# onion_dip_v2.net
KiCad netlist of a schematic drawn in EAGLE
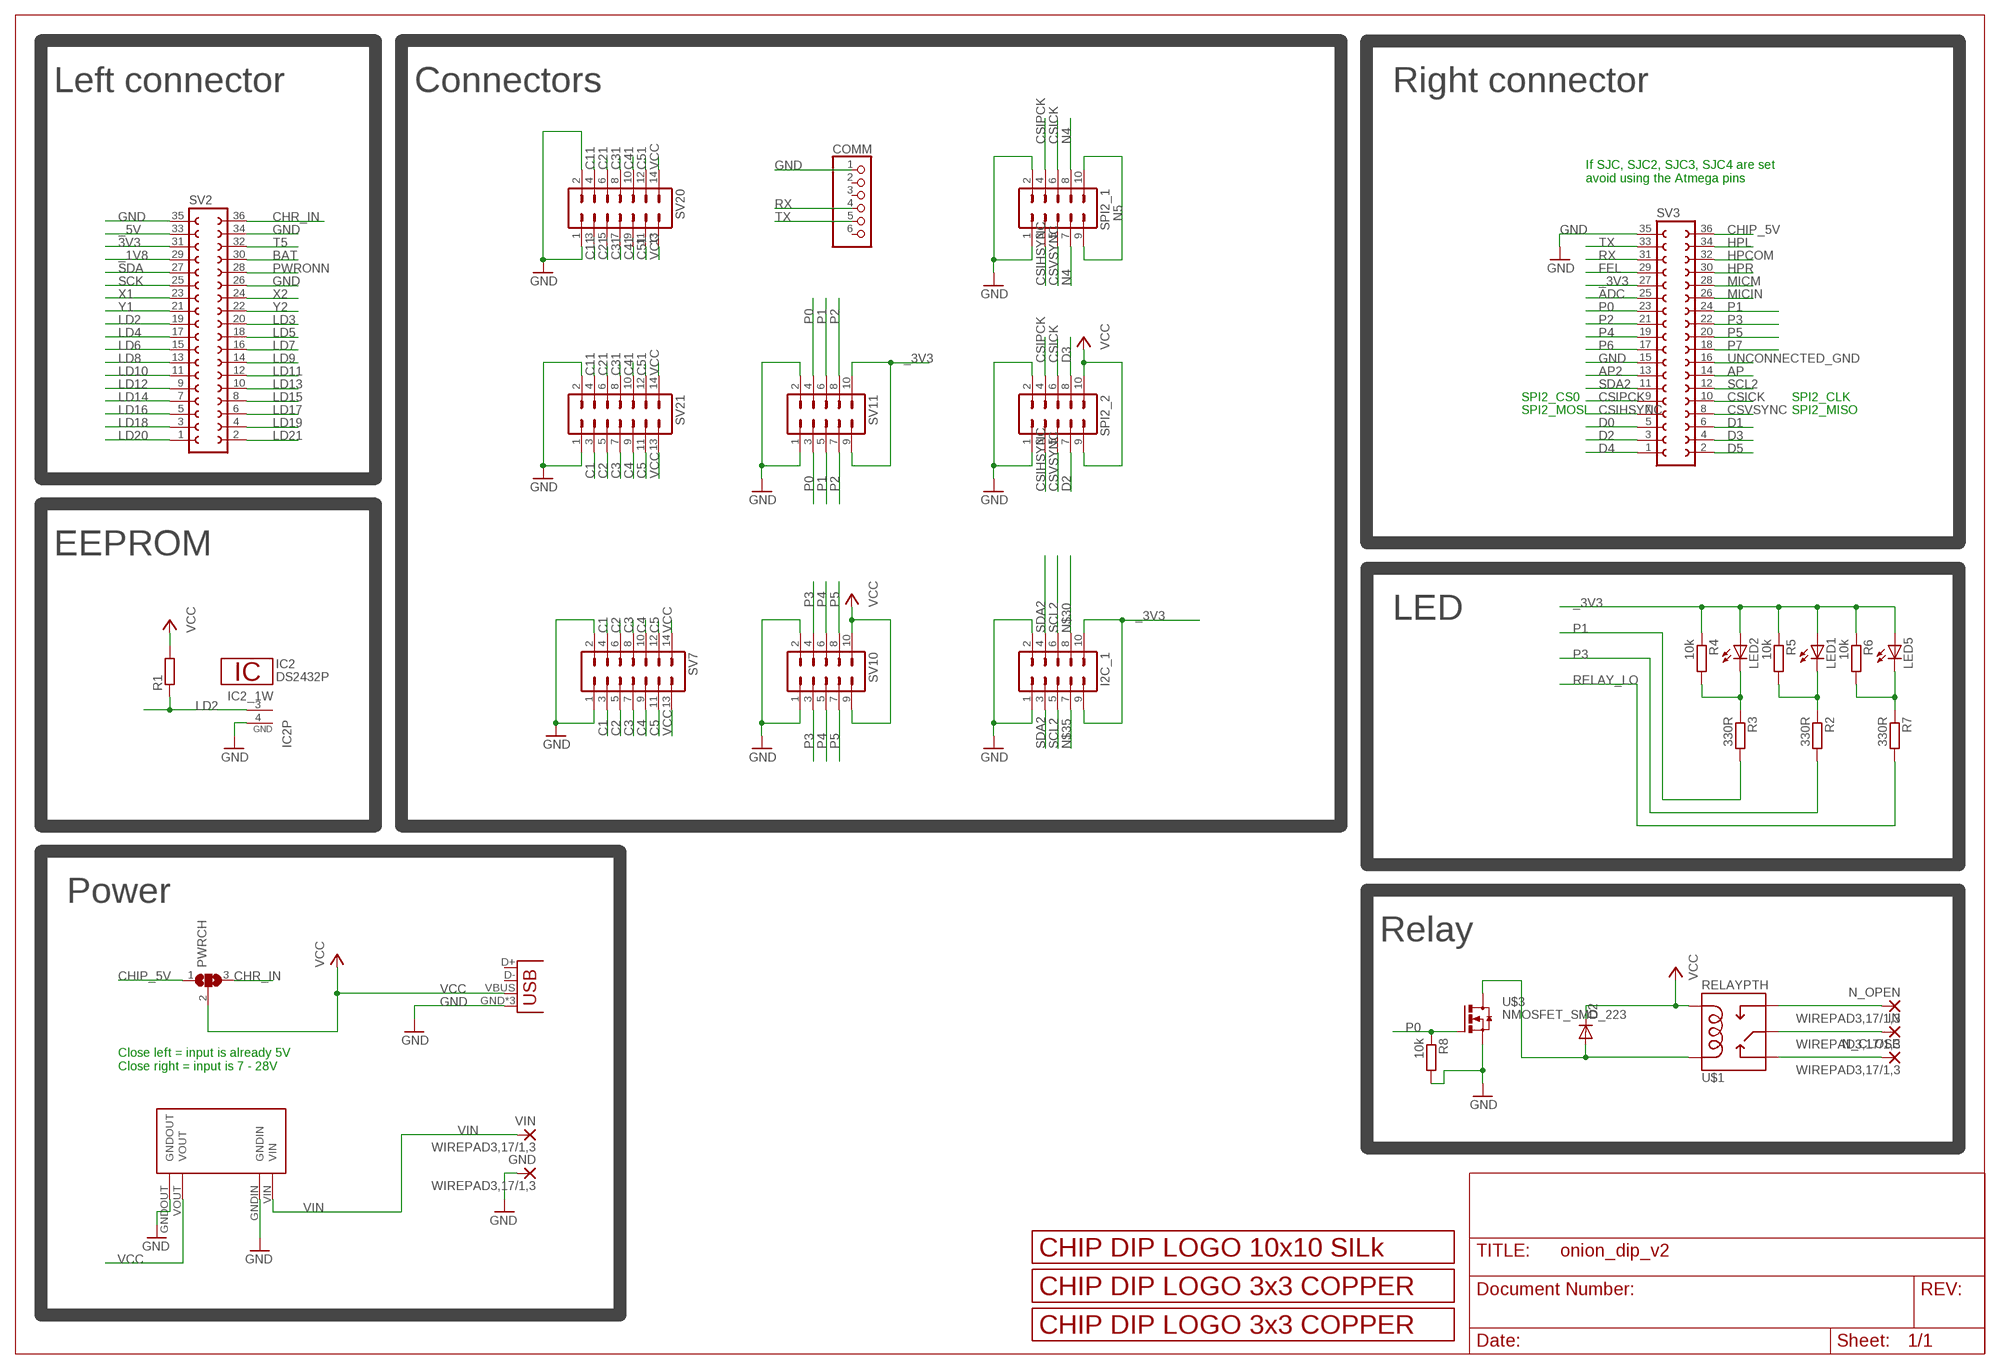
[diagram p0: schematic, sheet 1]

(export (version "E")
  (design (tool "Eeschema 10.0.6"))
  (components
    (comp (ref "COMM")
      (value "PINHD-1X6")
      (footprint "eagle-import:1X06")
      (libsource (lib "eagle-import") (part "PINHD-1X6"))
    )
    (comp (ref "D2")
      (value "DIODE-SMB")
      (footprint "eagle-import:SMB")
      (libsource (lib "eagle-import") (part "DIODE-SMB"))
    )
    (comp (ref "GND")
      (value "WIREPAD3,17/1,3")
      (footprint "eagle-import:3,17_1,3")
      (libsource (lib "eagle-import") (part "WIREPAD3,17/1,3"))
    )
    (comp (ref "I2C_1")
      (value "MA05-2")
      (footprint "eagle-import:MA05-2")
      (libsource (lib "eagle-import") (part "MA05-2"))
    )
    (comp (ref "IC2")
      (value "DS2432P")
      (footprint "eagle-import:TSOC6")
      (libsource (lib "eagle-import") (part "DS2432P"))
    )
    (comp (ref "IN")
      (value "WIREPAD3,17/1,3")
      (footprint "eagle-import:3,17_1,3")
      (libsource (lib "eagle-import") (part "WIREPAD3,17/1,3"))
    )
    (comp (ref "LED1")
      (value "LEDCHIP-LED0805")
      (footprint "eagle-import:CHIP-LED0805")
      (libsource (lib "eagle-import") (part "LEDCHIP-LED0805"))
    )
    (comp (ref "LED2")
      (value "LEDCHIP-LED0805")
      (footprint "eagle-import:CHIP-LED0805")
      (libsource (lib "eagle-import") (part "LEDCHIP-LED0805"))
    )
    (comp (ref "LED5")
      (value "LEDCHIP-LED0805")
      (footprint "eagle-import:CHIP-LED0805")
      (libsource (lib "eagle-import") (part "LEDCHIP-LED0805"))
    )
    (comp (ref "N_CLOSE")
      (value "WIREPAD3,17/1,3")
      (footprint "eagle-import:3,17_1,3")
      (libsource (lib "eagle-import") (part "WIREPAD3,17/1,3"))
    )
    (comp (ref "N_OPEN")
      (value "WIREPAD3,17/1,3")
      (footprint "eagle-import:3,17_1,3")
      (libsource (lib "eagle-import") (part "WIREPAD3,17/1,3"))
    )
    (comp (ref "PWRCH")
      (value "SJ2W")
      (footprint "eagle-import:SJ_2")
      (libsource (lib "eagle-import") (part "SJ2W"))
    )
    (comp (ref "R1")
      (value "R-EU_R0805")
      (footprint "eagle-import:R0805")
      (libsource (lib "eagle-import") (part "R-EU_R0805"))
    )
    (comp (ref "R2")
      (value "330R")
      (footprint "eagle-import:R0805")
      (libsource (lib "eagle-import") (part "R-EU_R0805"))
    )
    (comp (ref "R3")
      (value "330R")
      (footprint "eagle-import:R0805")
      (libsource (lib "eagle-import") (part "R-EU_R0805"))
    )
    (comp (ref "R4")
      (value "10k")
      (footprint "eagle-import:R0805")
      (libsource (lib "eagle-import") (part "R-EU_R0805"))
    )
    (comp (ref "R5")
      (value "10k")
      (footprint "eagle-import:R0805")
      (libsource (lib "eagle-import") (part "R-EU_R0805"))
    )
    (comp (ref "R6")
      (value "10k")
      (footprint "eagle-import:R0805")
      (libsource (lib "eagle-import") (part "R-EU_R0805"))
    )
    (comp (ref "R7")
      (value "330R")
      (footprint "eagle-import:R0805")
      (libsource (lib "eagle-import") (part "R-EU_R0805"))
    )
    (comp (ref "R8")
      (value "10k")
      (footprint "eagle-import:R0805")
      (libsource (lib "eagle-import") (part "R-EU_R0805"))
    )
    (comp (ref "SPI2_1")
      (value "MA05-2")
      (footprint "eagle-import:MA05-2")
      (libsource (lib "eagle-import") (part "MA05-2"))
    )
    (comp (ref "SPI2_2")
      (value "MA05-2")
      (footprint "eagle-import:MA05-2")
      (libsource (lib "eagle-import") (part "MA05-2"))
    )
    (comp (ref "SV2")
      (value "FE18-2")
      (footprint "eagle-import:FE18-2")
      (libsource (lib "eagle-import") (part "FE18-2"))
    )
    (comp (ref "SV3")
      (value "FE18-2")
      (footprint "eagle-import:FE18-2")
      (libsource (lib "eagle-import") (part "FE18-2"))
    )
    (comp (ref "SV7")
      (value "MA07-2")
      (footprint "eagle-import:MA07-2")
      (libsource (lib "eagle-import") (part "MA07-2"))
    )
    (comp (ref "SV10")
      (value "MA05-2")
      (footprint "eagle-import:MA05-2")
      (libsource (lib "eagle-import") (part "MA05-2"))
    )
    (comp (ref "SV11")
      (value "MA05-2")
      (footprint "eagle-import:MA05-2")
      (libsource (lib "eagle-import") (part "MA05-2"))
    )
    (comp (ref "SV20")
      (value "MA07-2")
      (footprint "eagle-import:MA07-2")
      (libsource (lib "eagle-import") (part "MA07-2"))
    )
    (comp (ref "SV21")
      (value "MA07-2")
      (footprint "eagle-import:MA07-2")
      (libsource (lib "eagle-import") (part "MA07-2"))
    )
    (comp (ref "U$1")
      (value "RELAYPTH")
      (footprint "eagle-import:SRD-05VDC-SL-C")
      (libsource (lib "eagle-import") (part "RELAYPTH"))
    )
    (comp (ref "U$3")
      (value "NMOSFET_SMD_223")
      (footprint "eagle-import:SOT223")
      (libsource (lib "eagle-import") (part "NMOSFET_SMD_223"))
    )
    (comp (ref "U$4")
      (value "LOGO_3X3_COPPER")
      (footprint "eagle-import:LOGO_3X3_COPPER")
      (libsource (lib "eagle-import") (part "LOGO_3X3_COPPER"))
    )
    (comp (ref "U$5")
      (value "LOGO_10X10_SILK")
      (footprint "eagle-import:LOGO_10X10_SILK")
      (libsource (lib "eagle-import") (part "LOGO_10X10_SILK"))
    )
    (comp (ref "U$6")
      (value "LOGO_3X3_COPPER")
      (footprint "eagle-import:LOGO_3X3_COPPER")
      (libsource (lib "eagle-import") (part "LOGO_3X3_COPPER"))
    )
    (comp (ref "U$9")
      (value "MP1584EN_FRAMELESS")
      (footprint "eagle-import:MP1584EN_FRAMELESS")
      (libsource (lib "eagle-import") (part "MP1584EN_FRAMELESS"))
    )
    (comp (ref "USB")
      (value "USBUSB-MICROB-SMT-DIP")
      (footprint "eagle-import:USB-MICROB-SMT-DIP")
      (libsource (lib "eagle-import") (part "USBUSB-MICROB-SMT-DIP"))
    )
    (comp (ref "VIN")
      (value "WIREPAD3,17/1,3")
      (footprint "eagle-import:3,17_1,3")
      (libsource (lib "eagle-import") (part "WIREPAD3,17/1,3"))
    )
  )
  (nets
    (net (code "1") (name "/3V3") (class "Default")
      (node (ref "SV2") (pin "31") (pinfunction "31_31") (pintype "passive"))
    )
    (net (code "2") (name "/ADC") (class "Default")
      (node (ref "SV3") (pin "25") (pinfunction "25_25") (pintype "passive"))
    )
    (net (code "3") (name "/AP") (class "Default")
      (node (ref "SV3") (pin "14") (pinfunction "14_14") (pintype "passive"))
    )
    (net (code "4") (name "/AP2") (class "Default")
      (node (ref "SV3") (pin "13") (pinfunction "13_13") (pintype "passive"))
    )
    (net (code "5") (name "/BAT") (class "Default")
      (node (ref "SV2") (pin "30") (pinfunction "30_30") (pintype "passive"))
    )
    (net (code "6") (name "/C1") (class "Default")
      (node (ref "SV21") (pin "3") (pinfunction "3_3") (pintype "passive"))
      (node (ref "SV7") (pin "3") (pinfunction "3_3") (pintype "passive"))
      (node (ref "SV7") (pin "4") (pinfunction "4_4") (pintype "passive"))
    )
    (net (code "7") (name "/C2") (class "Default")
      (node (ref "SV21") (pin "5") (pinfunction "5_5") (pintype "passive"))
      (node (ref "SV7") (pin "5") (pinfunction "5_5") (pintype "passive"))
      (node (ref "SV7") (pin "6") (pinfunction "6_6") (pintype "passive"))
    )
    (net (code "8") (name "/C3") (class "Default")
      (node (ref "SV21") (pin "7") (pinfunction "7_7") (pintype "passive"))
      (node (ref "SV7") (pin "7") (pinfunction "7_7") (pintype "passive"))
      (node (ref "SV7") (pin "8") (pinfunction "8_8") (pintype "passive"))
    )
    (net (code "9") (name "/C4") (class "Default")
      (node (ref "SV21") (pin "9") (pinfunction "9_9") (pintype "passive"))
      (node (ref "SV7") (pin "10") (pinfunction "10_10") (pintype "passive"))
      (node (ref "SV7") (pin "9") (pinfunction "9_9") (pintype "passive"))
    )
    (net (code "10") (name "/C5") (class "Default")
      (node (ref "SV21") (pin "11") (pinfunction "11_11") (pintype "passive"))
      (node (ref "SV7") (pin "11") (pinfunction "11_11") (pintype "passive"))
      (node (ref "SV7") (pin "12") (pinfunction "12_12") (pintype "passive"))
    )
    (net (code "11") (name "/C11") (class "Default")
      (node (ref "SV20") (pin "3") (pinfunction "3_3") (pintype "passive"))
      (node (ref "SV20") (pin "4") (pinfunction "4_4") (pintype "passive"))
      (node (ref "SV21") (pin "4") (pinfunction "4_4") (pintype "passive"))
    )
    (net (code "12") (name "/C21") (class "Default")
      (node (ref "SV20") (pin "5") (pinfunction "5_5") (pintype "passive"))
      (node (ref "SV20") (pin "6") (pinfunction "6_6") (pintype "passive"))
      (node (ref "SV21") (pin "6") (pinfunction "6_6") (pintype "passive"))
    )
    (net (code "13") (name "/C31") (class "Default")
      (node (ref "SV20") (pin "7") (pinfunction "7_7") (pintype "passive"))
      (node (ref "SV20") (pin "8") (pinfunction "8_8") (pintype "passive"))
      (node (ref "SV21") (pin "8") (pinfunction "8_8") (pintype "passive"))
    )
    (net (code "14") (name "/C41") (class "Default")
      (node (ref "SV20") (pin "10") (pinfunction "10_10") (pintype "passive"))
      (node (ref "SV20") (pin "9") (pinfunction "9_9") (pintype "passive"))
      (node (ref "SV21") (pin "10") (pinfunction "10_10") (pintype "passive"))
    )
    (net (code "15") (name "/C51") (class "Default")
      (node (ref "SV20") (pin "11") (pinfunction "11_11") (pintype "passive"))
      (node (ref "SV20") (pin "12") (pinfunction "12_12") (pintype "passive"))
      (node (ref "SV21") (pin "12") (pinfunction "12_12") (pintype "passive"))
    )
    (net (code "16") (name "/CHIP_5V") (class "Default")
      (node (ref "PWRCH") (pin "1") (pinfunction "1_1") (pintype "passive"))
      (node (ref "SV3") (pin "36") (pinfunction "36_36") (pintype "passive"))
    )
    (net (code "17") (name "/CHR_IN") (class "Default")
      (node (ref "PWRCH") (pin "3") (pinfunction "3_3") (pintype "passive"))
      (node (ref "SV2") (pin "36") (pinfunction "36_36") (pintype "passive"))
    )
    (net (code "18") (name "/CSICK") (class "Default")
      (node (ref "SPI2_1") (pin "6") (pinfunction "6_6") (pintype "passive"))
      (node (ref "SPI2_2") (pin "6") (pinfunction "6_6") (pintype "passive"))
      (node (ref "SV3") (pin "10") (pinfunction "10_10") (pintype "passive"))
    )
    (net (code "19") (name "/CSIHSYNC") (class "Default")
      (node (ref "SPI2_1") (pin "3") (pinfunction "3_3") (pintype "passive"))
      (node (ref "SPI2_2") (pin "3") (pinfunction "3_3") (pintype "passive"))
      (node (ref "SV3") (pin "7") (pinfunction "7_7") (pintype "passive"))
    )
    (net (code "20") (name "/CSIPCK") (class "Default")
      (node (ref "SPI2_1") (pin "4") (pinfunction "4_4") (pintype "passive"))
      (node (ref "SPI2_2") (pin "4") (pinfunction "4_4") (pintype "passive"))
      (node (ref "SV3") (pin "9") (pinfunction "9_9") (pintype "passive"))
    )
    (net (code "21") (name "/CSVSYNC") (class "Default")
      (node (ref "SPI2_1") (pin "5") (pinfunction "5_5") (pintype "passive"))
      (node (ref "SPI2_2") (pin "5") (pinfunction "5_5") (pintype "passive"))
      (node (ref "SV3") (pin "8") (pinfunction "8_8") (pintype "passive"))
    )
    (net (code "22") (name "/D0") (class "Default")
      (node (ref "SV3") (pin "5") (pinfunction "5_5") (pintype "passive"))
    )
    (net (code "23") (name "/D1") (class "Default")
      (node (ref "SV3") (pin "6") (pinfunction "6_6") (pintype "passive"))
    )
    (net (code "24") (name "/D2") (class "Default")
      (node (ref "SPI2_2") (pin "7") (pinfunction "7_7") (pintype "passive"))
      (node (ref "SV3") (pin "3") (pinfunction "3_3") (pintype "passive"))
    )
    (net (code "25") (name "/D3") (class "Default")
      (node (ref "SPI2_2") (pin "8") (pinfunction "8_8") (pintype "passive"))
      (node (ref "SV3") (pin "4") (pinfunction "4_4") (pintype "passive"))
    )
    (net (code "26") (name "/D4") (class "Default")
      (node (ref "SV3") (pin "1") (pinfunction "1_1") (pintype "passive"))
    )
    (net (code "27") (name "/D5") (class "Default")
      (node (ref "SV3") (pin "2") (pinfunction "2_2") (pintype "passive"))
    )
    (net (code "28") (name "/FEL") (class "Default")
      (node (ref "SV3") (pin "29") (pinfunction "29_29") (pintype "passive"))
    )
    (net (code "29") (name "/HPCOM") (class "Default")
      (node (ref "SV3") (pin "32") (pinfunction "32_32") (pintype "passive"))
    )
    (net (code "30") (name "/HPL") (class "Default")
      (node (ref "SV3") (pin "34") (pinfunction "34_34") (pintype "passive"))
    )
    (net (code "31") (name "/HPR") (class "Default")
      (node (ref "SV3") (pin "30") (pinfunction "30_30") (pintype "passive"))
    )
    (net (code "32") (name "/LD2") (class "Default")
      (node (ref "IC2") (pin "3") (pinfunction "1W_3") (pintype "power_in"))
      (node (ref "R1") (pin "1") (pinfunction "1_1") (pintype "passive"))
      (node (ref "SV2") (pin "19") (pinfunction "19_19") (pintype "passive"))
    )
    (net (code "33") (name "/LD3") (class "Default")
      (node (ref "SV2") (pin "20") (pinfunction "20_20") (pintype "passive"))
    )
    (net (code "34") (name "/LD4") (class "Default")
      (node (ref "SV2") (pin "17") (pinfunction "17_17") (pintype "passive"))
    )
    (net (code "35") (name "/LD5") (class "Default")
      (node (ref "SV2") (pin "18") (pinfunction "18_18") (pintype "passive"))
    )
    (net (code "36") (name "/LD6") (class "Default")
      (node (ref "SV2") (pin "15") (pinfunction "15_15") (pintype "passive"))
    )
    (net (code "37") (name "/LD7") (class "Default")
      (node (ref "SV2") (pin "16") (pinfunction "16_16") (pintype "passive"))
    )
    (net (code "38") (name "/LD8") (class "Default")
      (node (ref "SV2") (pin "13") (pinfunction "13_13") (pintype "passive"))
    )
    (net (code "39") (name "/LD9") (class "Default")
      (node (ref "SV2") (pin "14") (pinfunction "14_14") (pintype "passive"))
    )
    (net (code "40") (name "/LD10") (class "Default")
      (node (ref "SV2") (pin "11") (pinfunction "11_11") (pintype "passive"))
    )
    (net (code "41") (name "/LD11") (class "Default")
      (node (ref "SV2") (pin "12") (pinfunction "12_12") (pintype "passive"))
    )
    (net (code "42") (name "/LD12") (class "Default")
      (node (ref "SV2") (pin "9") (pinfunction "9_9") (pintype "passive"))
    )
    (net (code "43") (name "/LD13") (class "Default")
      (node (ref "SV2") (pin "10") (pinfunction "10_10") (pintype "passive"))
    )
    (net (code "44") (name "/LD14") (class "Default")
      (node (ref "SV2") (pin "7") (pinfunction "7_7") (pintype "passive"))
    )
    (net (code "45") (name "/LD15") (class "Default")
      (node (ref "SV2") (pin "8") (pinfunction "8_8") (pintype "passive"))
    )
    (net (code "46") (name "/LD16") (class "Default")
      (node (ref "SV2") (pin "5") (pinfunction "5_5") (pintype "passive"))
    )
    (net (code "47") (name "/LD17") (class "Default")
      (node (ref "SV2") (pin "6") (pinfunction "6_6") (pintype "passive"))
    )
    (net (code "48") (name "/LD18") (class "Default")
      (node (ref "SV2") (pin "3") (pinfunction "3_3") (pintype "passive"))
    )
    (net (code "49") (name "/LD19") (class "Default")
      (node (ref "SV2") (pin "4") (pinfunction "4_4") (pintype "passive"))
    )
    (net (code "50") (name "/LD20") (class "Default")
      (node (ref "SV2") (pin "1") (pinfunction "1_1") (pintype "passive"))
    )
    (net (code "51") (name "/LD21") (class "Default")
      (node (ref "SV2") (pin "2") (pinfunction "2_2") (pintype "passive"))
    )
    (net (code "52") (name "/MICIN") (class "Default")
      (node (ref "SV3") (pin "26") (pinfunction "26_26") (pintype "passive"))
    )
    (net (code "53") (name "/MICM") (class "Default")
      (node (ref "SV3") (pin "28") (pinfunction "28_28") (pintype "passive"))
    )
    (net (code "54") (name "/N$30") (class "Default")
      (node (ref "I2C_1") (pin "8") (pinfunction "8_8") (pintype "passive"))
    )
    (net (code "55") (name "/N$35") (class "Default")
      (node (ref "I2C_1") (pin "7") (pinfunction "7_7") (pintype "passive"))
    )
    (net (code "56") (name "/N4") (class "Default")
      (node (ref "SPI2_1") (pin "7") (pinfunction "7_7") (pintype "passive"))
      (node (ref "SPI2_1") (pin "8") (pinfunction "8_8") (pintype "passive"))
    )
    (net (code "57") (name "/N5") (class "Default")
      (node (ref "SPI2_1") (pin "10") (pinfunction "10_10") (pintype "passive"))
      (node (ref "SPI2_1") (pin "9") (pinfunction "9_9") (pintype "passive"))
    )
    (net (code "58") (name "/P0") (class "Default")
      (node (ref "R8") (pin "1") (pinfunction "1_1") (pintype "passive"))
      (node (ref "SV11") (pin "3") (pinfunction "3_3") (pintype "passive"))
      (node (ref "SV11") (pin "4") (pinfunction "4_4") (pintype "passive"))
      (node (ref "SV3") (pin "23") (pinfunction "23_23") (pintype "passive"))
      (node (ref "U$3") (pin "1") (pinfunction "G_1") (pintype "passive"))
    )
    (net (code "59") (name "/P1") (class "Default")
      (node (ref "R3") (pin "2") (pinfunction "2_2") (pintype "passive"))
      (node (ref "SV11") (pin "5") (pinfunction "5_5") (pintype "passive"))
      (node (ref "SV11") (pin "6") (pinfunction "6_6") (pintype "passive"))
      (node (ref "SV3") (pin "24") (pinfunction "24_24") (pintype "passive"))
    )
    (net (code "60") (name "/P2") (class "Default")
      (node (ref "SV11") (pin "7") (pinfunction "7_7") (pintype "passive"))
      (node (ref "SV11") (pin "8") (pinfunction "8_8") (pintype "passive"))
      (node (ref "SV3") (pin "21") (pinfunction "21_21") (pintype "passive"))
    )
    (net (code "61") (name "/P3") (class "Default")
      (node (ref "R2") (pin "2") (pinfunction "2_2") (pintype "passive"))
      (node (ref "SV10") (pin "3") (pinfunction "3_3") (pintype "passive"))
      (node (ref "SV10") (pin "4") (pinfunction "4_4") (pintype "passive"))
      (node (ref "SV3") (pin "22") (pinfunction "22_22") (pintype "passive"))
    )
    (net (code "62") (name "/P4") (class "Default")
      (node (ref "SV10") (pin "5") (pinfunction "5_5") (pintype "passive"))
      (node (ref "SV10") (pin "6") (pinfunction "6_6") (pintype "passive"))
      (node (ref "SV3") (pin "19") (pinfunction "19_19") (pintype "passive"))
    )
    (net (code "63") (name "/P5") (class "Default")
      (node (ref "SV10") (pin "7") (pinfunction "7_7") (pintype "passive"))
      (node (ref "SV10") (pin "8") (pinfunction "8_8") (pintype "passive"))
      (node (ref "SV3") (pin "20") (pinfunction "20_20") (pintype "passive"))
    )
    (net (code "64") (name "/P6") (class "Default")
      (node (ref "SV3") (pin "17") (pinfunction "17_17") (pintype "passive"))
    )
    (net (code "65") (name "/P7") (class "Default")
      (node (ref "SV3") (pin "18") (pinfunction "18_18") (pintype "passive"))
    )
    (net (code "66") (name "/PWRONN") (class "Default")
      (node (ref "SV2") (pin "28") (pinfunction "28_28") (pintype "passive"))
    )
    (net (code "67") (name "/RELAY_LO") (class "Default")
      (node (ref "D2") (pin "A") (pinfunction "A_A") (pintype "passive"))
      (node (ref "R7") (pin "2") (pinfunction "2_2") (pintype "passive"))
      (node (ref "U$1") (pin "COIL1") (pinfunction "COIL1_COIL1") (pintype "bidirectional"))
      (node (ref "U$3") (pin "2") (pinfunction "D_2") (pintype "passive"))
      (node (ref "U$3") (pin "4") (pinfunction "D_4") (pintype "passive"))
    )
    (net (code "68") (name "/RX") (class "Default")
      (node (ref "COMM") (pin "4") (pinfunction "4_4") (pintype "passive"))
      (node (ref "SV3") (pin "31") (pinfunction "31_31") (pintype "passive"))
    )
    (net (code "69") (name "/SCK") (class "Default")
      (node (ref "SV2") (pin "25") (pinfunction "25_25") (pintype "passive"))
    )
    (net (code "70") (name "/SCL2") (class "Default")
      (node (ref "I2C_1") (pin "5") (pinfunction "5_5") (pintype "passive"))
      (node (ref "I2C_1") (pin "6") (pinfunction "6_6") (pintype "passive"))
      (node (ref "SV3") (pin "12") (pinfunction "12_12") (pintype "passive"))
    )
    (net (code "71") (name "/SDA") (class "Default")
      (node (ref "SV2") (pin "27") (pinfunction "27_27") (pintype "passive"))
    )
    (net (code "72") (name "/SDA2") (class "Default")
      (node (ref "I2C_1") (pin "3") (pinfunction "3_3") (pintype "passive"))
      (node (ref "I2C_1") (pin "4") (pinfunction "4_4") (pintype "passive"))
      (node (ref "SV3") (pin "11") (pinfunction "11_11") (pintype "passive"))
    )
    (net (code "73") (name "/T5") (class "Default")
      (node (ref "SV2") (pin "32") (pinfunction "32_32") (pintype "passive"))
    )
    (net (code "74") (name "/TX") (class "Default")
      (node (ref "COMM") (pin "5") (pinfunction "5_5") (pintype "passive"))
      (node (ref "SV3") (pin "33") (pinfunction "33_33") (pintype "passive"))
    )
    (net (code "75") (name "/UNCONNECTED_GND") (class "Default")
      (node (ref "SV3") (pin "16") (pinfunction "16_16") (pintype "passive"))
    )
    (net (code "76") (name "/VIN") (class "Default")
      (node (ref "U$9") (pin "VIN") (pinfunction "VIN_VIN") (pintype "power_in"))
      (node (ref "VIN") (pin "1") (pinfunction "P_1") (pintype "passive"))
    )
    (net (code "77") (name "/X1") (class "Default")
      (node (ref "SV2") (pin "23") (pinfunction "23_23") (pintype "passive"))
    )
    (net (code "78") (name "/X2") (class "Default")
      (node (ref "SV2") (pin "24") (pinfunction "24_24") (pintype "passive"))
    )
    (net (code "79") (name "/Y1") (class "Default")
      (node (ref "SV2") (pin "21") (pinfunction "21_21") (pintype "passive"))
    )
    (net (code "80") (name "/Y2") (class "Default")
      (node (ref "SV2") (pin "22") (pinfunction "22_22") (pintype "passive"))
    )
    (net (code "81") (name "/_1V8") (class "Default")
      (node (ref "SV2") (pin "29") (pinfunction "29_29") (pintype "passive"))
    )
    (net (code "82") (name "/_3V3") (class "Default")
      (node (ref "I2C_1") (pin "10") (pinfunction "10_10") (pintype "passive"))
      (node (ref "I2C_1") (pin "9") (pinfunction "9_9") (pintype "passive"))
      (node (ref "LED1") (pin "A") (pinfunction "A_A") (pintype "passive"))
      (node (ref "LED2") (pin "A") (pinfunction "A_A") (pintype "passive"))
      (node (ref "LED5") (pin "A") (pinfunction "A_A") (pintype "passive"))
      (node (ref "R4") (pin "1") (pinfunction "1_1") (pintype "passive"))
      (node (ref "R5") (pin "1") (pinfunction "1_1") (pintype "passive"))
      (node (ref "R6") (pin "1") (pinfunction "1_1") (pintype "passive"))
      (node (ref "SV11") (pin "10") (pinfunction "10_10") (pintype "passive"))
      (node (ref "SV11") (pin "9") (pinfunction "9_9") (pintype "passive"))
      (node (ref "SV3") (pin "27") (pinfunction "27_27") (pintype "passive"))
    )
    (net (code "83") (name "/_5V") (class "Default")
      (node (ref "SV2") (pin "33") (pinfunction "33_33") (pintype "passive"))
    )
    (net (code "84") (name "GND") (class "Default")
      (node (ref "COMM") (pin "1") (pinfunction "1_1") (pintype "passive"))
      (node (ref "GND") (pin "1") (pinfunction "P_1") (pintype "passive"))
      (node (ref "I2C_1") (pin "1") (pinfunction "1_1") (pintype "passive"))
      (node (ref "I2C_1") (pin "2") (pinfunction "2_2") (pintype "passive"))
      (node (ref "IC2") (pin "4") (pinfunction "GND_4") (pintype "power_in"))
      (node (ref "R8") (pin "2") (pinfunction "2_2") (pintype "passive"))
      (node (ref "SPI2_1") (pin "1") (pinfunction "1_1") (pintype "passive"))
      (node (ref "SPI2_1") (pin "2") (pinfunction "2_2") (pintype "passive"))
      (node (ref "SPI2_2") (pin "1") (pinfunction "1_1") (pintype "passive"))
      (node (ref "SPI2_2") (pin "2") (pinfunction "2_2") (pintype "passive"))
      (node (ref "SV10") (pin "1") (pinfunction "1_1") (pintype "passive"))
      (node (ref "SV10") (pin "2") (pinfunction "2_2") (pintype "passive"))
      (node (ref "SV11") (pin "1") (pinfunction "1_1") (pintype "passive"))
      (node (ref "SV11") (pin "2") (pinfunction "2_2") (pintype "passive"))
      (node (ref "SV2") (pin "26") (pinfunction "26_26") (pintype "passive"))
      (node (ref "SV2") (pin "34") (pinfunction "34_34") (pintype "passive"))
      (node (ref "SV2") (pin "35") (pinfunction "35_35") (pintype "passive"))
      (node (ref "SV20") (pin "1") (pinfunction "1_1") (pintype "passive"))
      (node (ref "SV20") (pin "2") (pinfunction "2_2") (pintype "passive"))
      (node (ref "SV21") (pin "1") (pinfunction "1_1") (pintype "passive"))
      (node (ref "SV21") (pin "2") (pinfunction "2_2") (pintype "passive"))
      (node (ref "SV3") (pin "15") (pinfunction "15_15") (pintype "passive"))
      (node (ref "SV3") (pin "35") (pinfunction "35_35") (pintype "passive"))
      (node (ref "SV7") (pin "1") (pinfunction "1_1") (pintype "passive"))
      (node (ref "SV7") (pin "2") (pinfunction "2_2") (pintype "passive"))
      (node (ref "U$3") (pin "3") (pinfunction "S_3") (pintype "passive"))
      (node (ref "U$9") (pin "GNDIN") (pinfunction "GNDIN_GNDIN") (pintype "power_in"))
      (node (ref "U$9") (pin "GNDOUT") (pinfunction "GNDOUT_GNDOUT") (pintype "power_in"))
      (node (ref "USB") (pin "GND") (pinfunction "GND_GND") (pintype "bidirectional"))
      (node (ref "USB") (pin "MT1") (pinfunction "GND_MT1") (pintype "bidirectional"))
      (node (ref "USB") (pin "MT2") (pinfunction "GND_MT2") (pintype "bidirectional"))
    )
    (net (code "85") (name "Net-(IN-P)") (class "Default")
      (node (ref "IN") (pin "1") (pinfunction "P_1") (pintype "passive"))
      (node (ref "U$1") (pin "SWCOMMON") (pinfunction "SWCOMMON_SWCOMMON") (pintype "bidirectional"))
    )
    (net (code "86") (name "Net-(LED1-PadC)") (class "Default")
      (node (ref "LED1") (pin "C") (pinfunction "C_C") (pintype "passive"))
      (node (ref "R2") (pin "1") (pinfunction "1_1") (pintype "passive"))
      (node (ref "R5") (pin "2") (pinfunction "2_2") (pintype "passive"))
    )
    (net (code "87") (name "Net-(LED2-PadC)") (class "Default")
      (node (ref "LED2") (pin "C") (pinfunction "C_C") (pintype "passive"))
      (node (ref "R3") (pin "1") (pinfunction "1_1") (pintype "passive"))
      (node (ref "R4") (pin "2") (pinfunction "2_2") (pintype "passive"))
    )
    (net (code "88") (name "Net-(LED5-PadC)") (class "Default")
      (node (ref "LED5") (pin "C") (pinfunction "C_C") (pintype "passive"))
      (node (ref "R6") (pin "2") (pinfunction "2_2") (pintype "passive"))
      (node (ref "R7") (pin "1") (pinfunction "1_1") (pintype "passive"))
    )
    (net (code "89") (name "Net-(N_CLOSE-P)") (class "Default")
      (node (ref "N_CLOSE") (pin "1") (pinfunction "P_1") (pintype "passive"))
      (node (ref "U$1") (pin "SWCLOSED") (pinfunction "SWCLOSE_SWCLOSED") (pintype "bidirectional"))
    )
    (net (code "90") (name "Net-(N_OPEN-P)") (class "Default")
      (node (ref "N_OPEN") (pin "1") (pinfunction "P_1") (pintype "passive"))
      (node (ref "U$1") (pin "SWOPEN") (pinfunction "SWOPEN_SWOPEN") (pintype "bidirectional"))
    )
    (net (code "91") (name "VCC") (class "Default")
      (node (ref "D2") (pin "C") (pinfunction "C_C") (pintype "passive"))
      (node (ref "PWRCH") (pin "2") (pinfunction "2_2") (pintype "passive"))
      (node (ref "R1") (pin "2") (pinfunction "2_2") (pintype "passive"))
      (node (ref "SPI2_2") (pin "10") (pinfunction "10_10") (pintype "passive"))
      (node (ref "SPI2_2") (pin "9") (pinfunction "9_9") (pintype "passive"))
      (node (ref "SV10") (pin "10") (pinfunction "10_10") (pintype "passive"))
      (node (ref "SV10") (pin "9") (pinfunction "9_9") (pintype "passive"))
      (node (ref "SV20") (pin "13") (pinfunction "13_13") (pintype "passive"))
      (node (ref "SV20") (pin "14") (pinfunction "14_14") (pintype "passive"))
      (node (ref "SV21") (pin "13") (pinfunction "13_13") (pintype "passive"))
      (node (ref "SV21") (pin "14") (pinfunction "14_14") (pintype "passive"))
      (node (ref "SV7") (pin "13") (pinfunction "13_13") (pintype "passive"))
      (node (ref "SV7") (pin "14") (pinfunction "14_14") (pintype "passive"))
      (node (ref "U$1") (pin "COIL0") (pinfunction "COIL0_COIL0") (pintype "bidirectional"))
      (node (ref "U$9") (pin "VOUT") (pinfunction "VOUT_VOUT") (pintype "power_in"))
      (node (ref "USB") (pin "VBUS") (pinfunction "VBUS_VBUS") (pintype "bidirectional"))
    )
    (net (code "92") (name "unconnected-(COMM-Pad2)") (class "Default")
      (node (ref "COMM") (pin "2") (pinfunction "2_2") (pintype "passive"))
    )
    (net (code "93") (name "unconnected-(COMM-Pad3)") (class "Default")
      (node (ref "COMM") (pin "3") (pinfunction "3_3") (pintype "passive"))
    )
    (net (code "94") (name "unconnected-(COMM-Pad6)") (class "Default")
      (node (ref "COMM") (pin "6") (pinfunction "6_6") (pintype "passive"))
    )
    (net (code "95") (name "unconnected-(USB-PadD+)") (class "Default")
      (node (ref "USB") (pin "D+") (pinfunction "D+_D+") (pintype "bidirectional"))
    )
    (net (code "96") (name "unconnected-(USB-PadD-)") (class "Default")
      (node (ref "USB") (pin "D-") (pinfunction "D-_D-") (pintype "bidirectional"))
    )
  )
)
